# Archimedes_Surucu_Cift_Cikis.net
KiCad netlist of a schematic drawn in Altium Designer
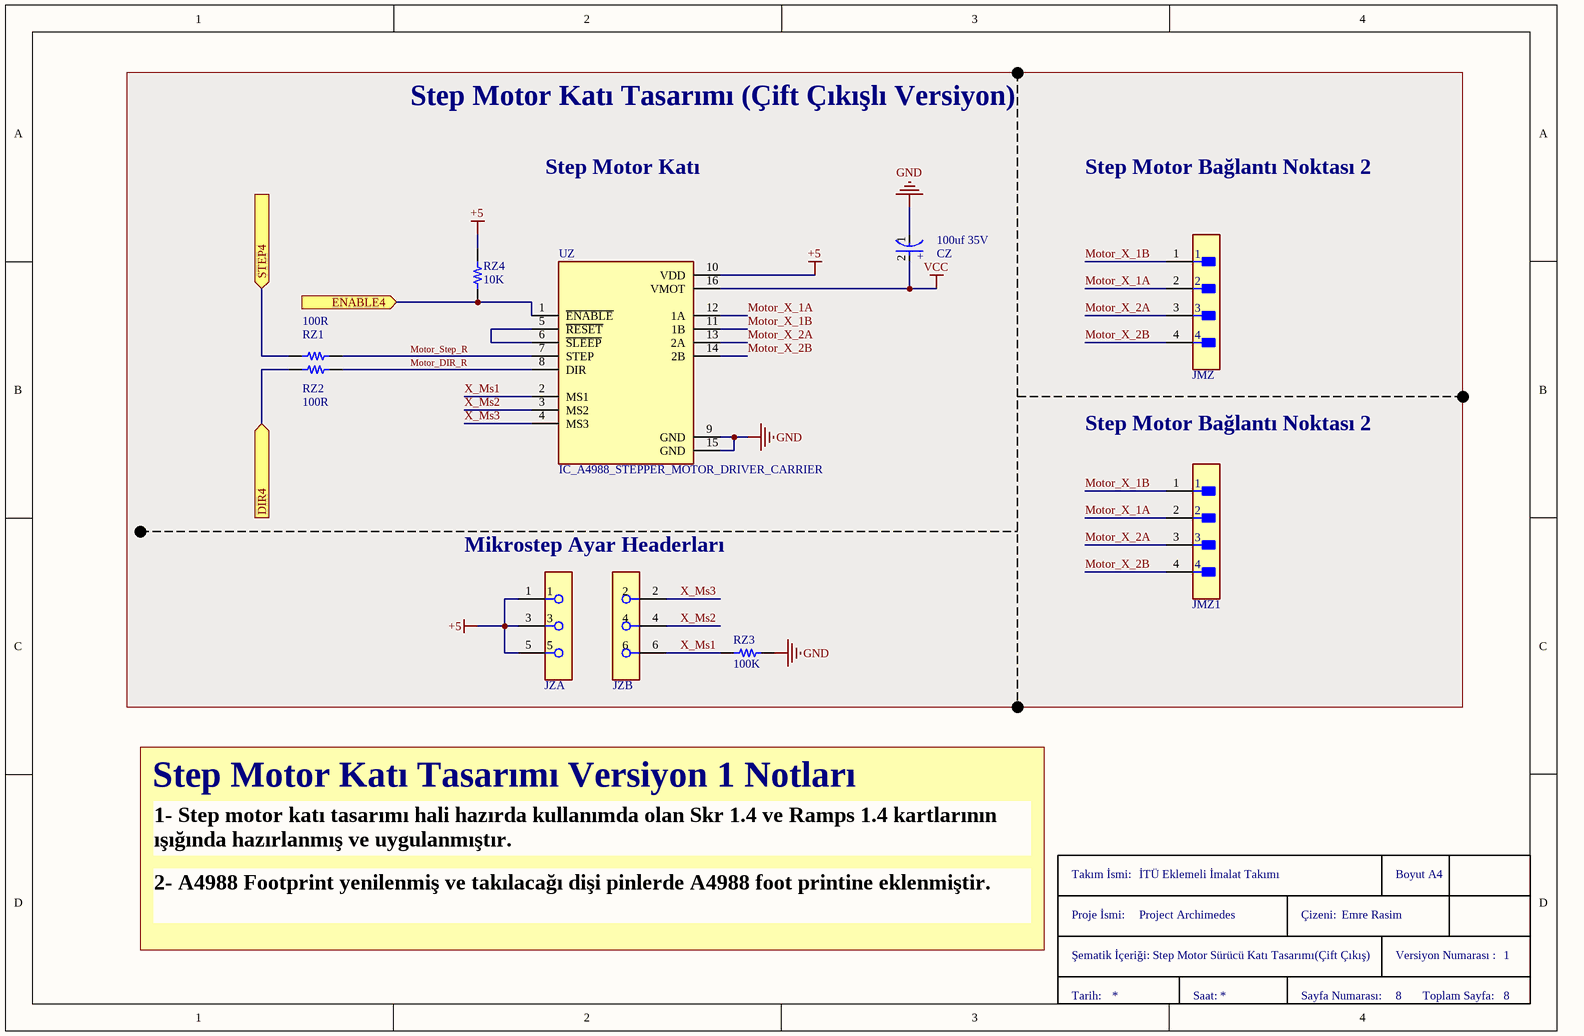
[diagram p0: Archimedes_Surucu_Cift_Cikis.SchDoc]

(export (version "E")
  (design (tool "Eeschema 10.0.6"))
  (components
    (comp (ref "CZ")
      (value "100uf 35V")
      (footprint "C_Smd_D6.3_H_7.7_Electrolytic_Cap")
      (description "electrolytic capacitor with 100 uf and 35 volt rating")
      (libsource (lib "EKIM_Team_Main") (part "C_smd_D6.3_H7.7"))
    )
    (comp (ref "JMZ")
      (value "2.5 mm locked")
      (footprint "CON_2.5MM_4_LEAD_180_LOCKED")
      (description "2.5 mm 4 lead locked connector")
      (libsource (lib "EKIM_Team_Main") (part "Con_2.5mm_4_lead_180_locked"))
    )
    (comp (ref "JMZ1")
      (value "2.5 mm locked")
      (footprint "CON_2.5MM_4_LEAD_180_LOCKED")
      (description "2.5 mm 4 lead locked connector")
      (libsource (lib "EKIM_Team_Main") (part "Con_2.5mm_4_lead_180_locked"))
    )
    (comp (ref "JZ")
      (value "Con_3*2_Male_Header")
      (footprint "Con_3*2_Male_header")
      (description "3*2 male header")
      (libsource (lib "") (part "Con_3*2_Male_Header_1"))
    )
    (comp (ref "RZ1")
      (value "100R")
      (footprint "RES 0805/2012")
      (description "100 R ohm Resistor  with 805 pack and %1 tolerance rating")
      (libsource (lib "Pasifler") (part "Resistor 805"))
    )
    (comp (ref "RZ2")
      (value "100R")
      (footprint "RES 0805/2012")
      (description "100 R ohm Resistor  with 805 pack and %1 tolerance rating")
      (libsource (lib "Pasifler") (part "Resistor 805"))
    )
    (comp (ref "RZ3")
      (value "100K")
      (footprint "RES 0805/2012")
      (description "100 K ohm Resistor  with 805 pack and %1 tolerance rating")
      (libsource (lib "Pasifler") (part "Resistor 805"))
    )
    (comp (ref "RZ4")
      (value "10K")
      (footprint "RES 0805/2012")
      (description "10 K ohm Resistor  with 805 pack and %1 tolerance rating")
      (libsource (lib "Pasifler") (part "Resistor 805"))
    )
    (comp (ref "UZ")
      (value "IC_A4988_STEPPER_MOTOR_DRIVER_CARRIER")
      (footprint "IC_A4988_STEPPER_MOTOR_DRIVER_CARRIER")
      (description "Stepper motor controler; IC: A4988; 1A; Uin mot: 8Ã·35V")
      (fields (field (name "MP") "A4988_STEPPER_MOTOR_DRIVER_CARRIER"))
      (libsource (lib "Buck") (part "IC_A4988_STEPPER_MOTOR_DRIVER_CARRIER"))
    )
  )
  (nets
    (net (code "1") (name "+5") (class "Default")
      (node (ref "JZ") (pin "1") (pinfunction "1_1") (pintype "passive"))
      (node (ref "JZ") (pin "3") (pinfunction "3_3") (pintype "passive"))
      (node (ref "JZ") (pin "5") (pinfunction "5_5") (pintype "passive"))
      (node (ref "RZ4") (pin "2") (pinfunction "2_2") (pintype "passive"))
      (node (ref "UZ") (pin "10") (pinfunction "VDD_10") (pintype "passive"))
    )
    (net (code "2") (name "/DIR4") (class "Default")
      (node (ref "RZ2") (pin "1") (pinfunction "1_1") (pintype "passive"))
    )
    (net (code "3") (name "/ENABLE4") (class "Default")
      (node (ref "RZ4") (pin "1") (pinfunction "1_1") (pintype "passive"))
      (node (ref "UZ") (pin "1") (pinfunction "~{ENABLE}_1") (pintype "passive"))
    )
    (net (code "4") (name "/Motor_DIR_R") (class "Default")
      (node (ref "RZ2") (pin "2") (pinfunction "2_2") (pintype "passive"))
      (node (ref "UZ") (pin "8") (pinfunction "DIR_8") (pintype "passive"))
    )
    (net (code "5") (name "/Motor_Step_R") (class "Default")
      (node (ref "RZ1") (pin "2") (pinfunction "2_2") (pintype "passive"))
      (node (ref "UZ") (pin "7") (pinfunction "STEP_7") (pintype "passive"))
    )
    (net (code "6") (name "/Motor_X_1A") (class "Default")
      (node (ref "JMZ") (pin "2") (pinfunction "2_2") (pintype "passive"))
      (node (ref "JMZ1") (pin "2") (pinfunction "2_2") (pintype "passive"))
      (node (ref "UZ") (pin "12") (pinfunction "1A_12") (pintype "passive"))
    )
    (net (code "7") (name "/Motor_X_1B") (class "Default")
      (node (ref "JMZ") (pin "1") (pinfunction "1_1") (pintype "passive"))
      (node (ref "JMZ1") (pin "1") (pinfunction "1_1") (pintype "passive"))
      (node (ref "UZ") (pin "11") (pinfunction "1B_11") (pintype "passive"))
    )
    (net (code "8") (name "/Motor_X_2A") (class "Default")
      (node (ref "JMZ") (pin "3") (pinfunction "3_3") (pintype "passive"))
      (node (ref "JMZ1") (pin "3") (pinfunction "3_3") (pintype "passive"))
      (node (ref "UZ") (pin "13") (pinfunction "2A_13") (pintype "passive"))
    )
    (net (code "9") (name "/Motor_X_2B") (class "Default")
      (node (ref "JMZ") (pin "4") (pinfunction "4_4") (pintype "passive"))
      (node (ref "JMZ1") (pin "4") (pinfunction "4_4") (pintype "passive"))
      (node (ref "UZ") (pin "14") (pinfunction "2B_14") (pintype "passive"))
    )
    (net (code "10") (name "/STEP4") (class "Default")
      (node (ref "RZ1") (pin "1") (pinfunction "1_1") (pintype "passive"))
    )
    (net (code "11") (name "/X_Ms1") (class "Default")
      (node (ref "JZ") (pin "6") (pinfunction "6_6") (pintype "passive"))
      (node (ref "RZ3") (pin "1") (pinfunction "1_1") (pintype "passive"))
      (node (ref "UZ") (pin "2") (pinfunction "MS1_2") (pintype "passive"))
    )
    (net (code "12") (name "/X_Ms2") (class "Default")
      (node (ref "JZ") (pin "4") (pinfunction "4_4") (pintype "passive"))
      (node (ref "UZ") (pin "3") (pinfunction "MS2_3") (pintype "passive"))
    )
    (net (code "13") (name "/X_Ms3") (class "Default")
      (node (ref "JZ") (pin "2") (pinfunction "2_2") (pintype "passive"))
      (node (ref "UZ") (pin "4") (pinfunction "MS3_4") (pintype "passive"))
    )
    (net (code "14") (name "GND") (class "Default")
      (node (ref "CZ") (pin "1") (pinfunction "C_1") (pintype "passive"))
      (node (ref "RZ3") (pin "2") (pinfunction "2_2") (pintype "passive"))
      (node (ref "UZ") (pin "15") (pinfunction "GND_15") (pintype "power_in"))
      (node (ref "UZ") (pin "9") (pinfunction "GND_9") (pintype "power_in"))
    )
    (net (code "15") (name "Net-(UZ-~{RESET})") (class "Default")
      (node (ref "UZ") (pin "5") (pinfunction "~{RESET}_5") (pintype "passive"))
      (node (ref "UZ") (pin "6") (pinfunction "~{SLEEP}_6") (pintype "passive"))
    )
    (net (code "16") (name "VCC") (class "Default")
      (node (ref "CZ") (pin "2") (pinfunction "A_2") (pintype "passive"))
      (node (ref "UZ") (pin "16") (pinfunction "VMOT_16") (pintype "passive"))
    )
  )
)
